# DXP.net
KiCad netlist of a schematic drawn in Altium Designer
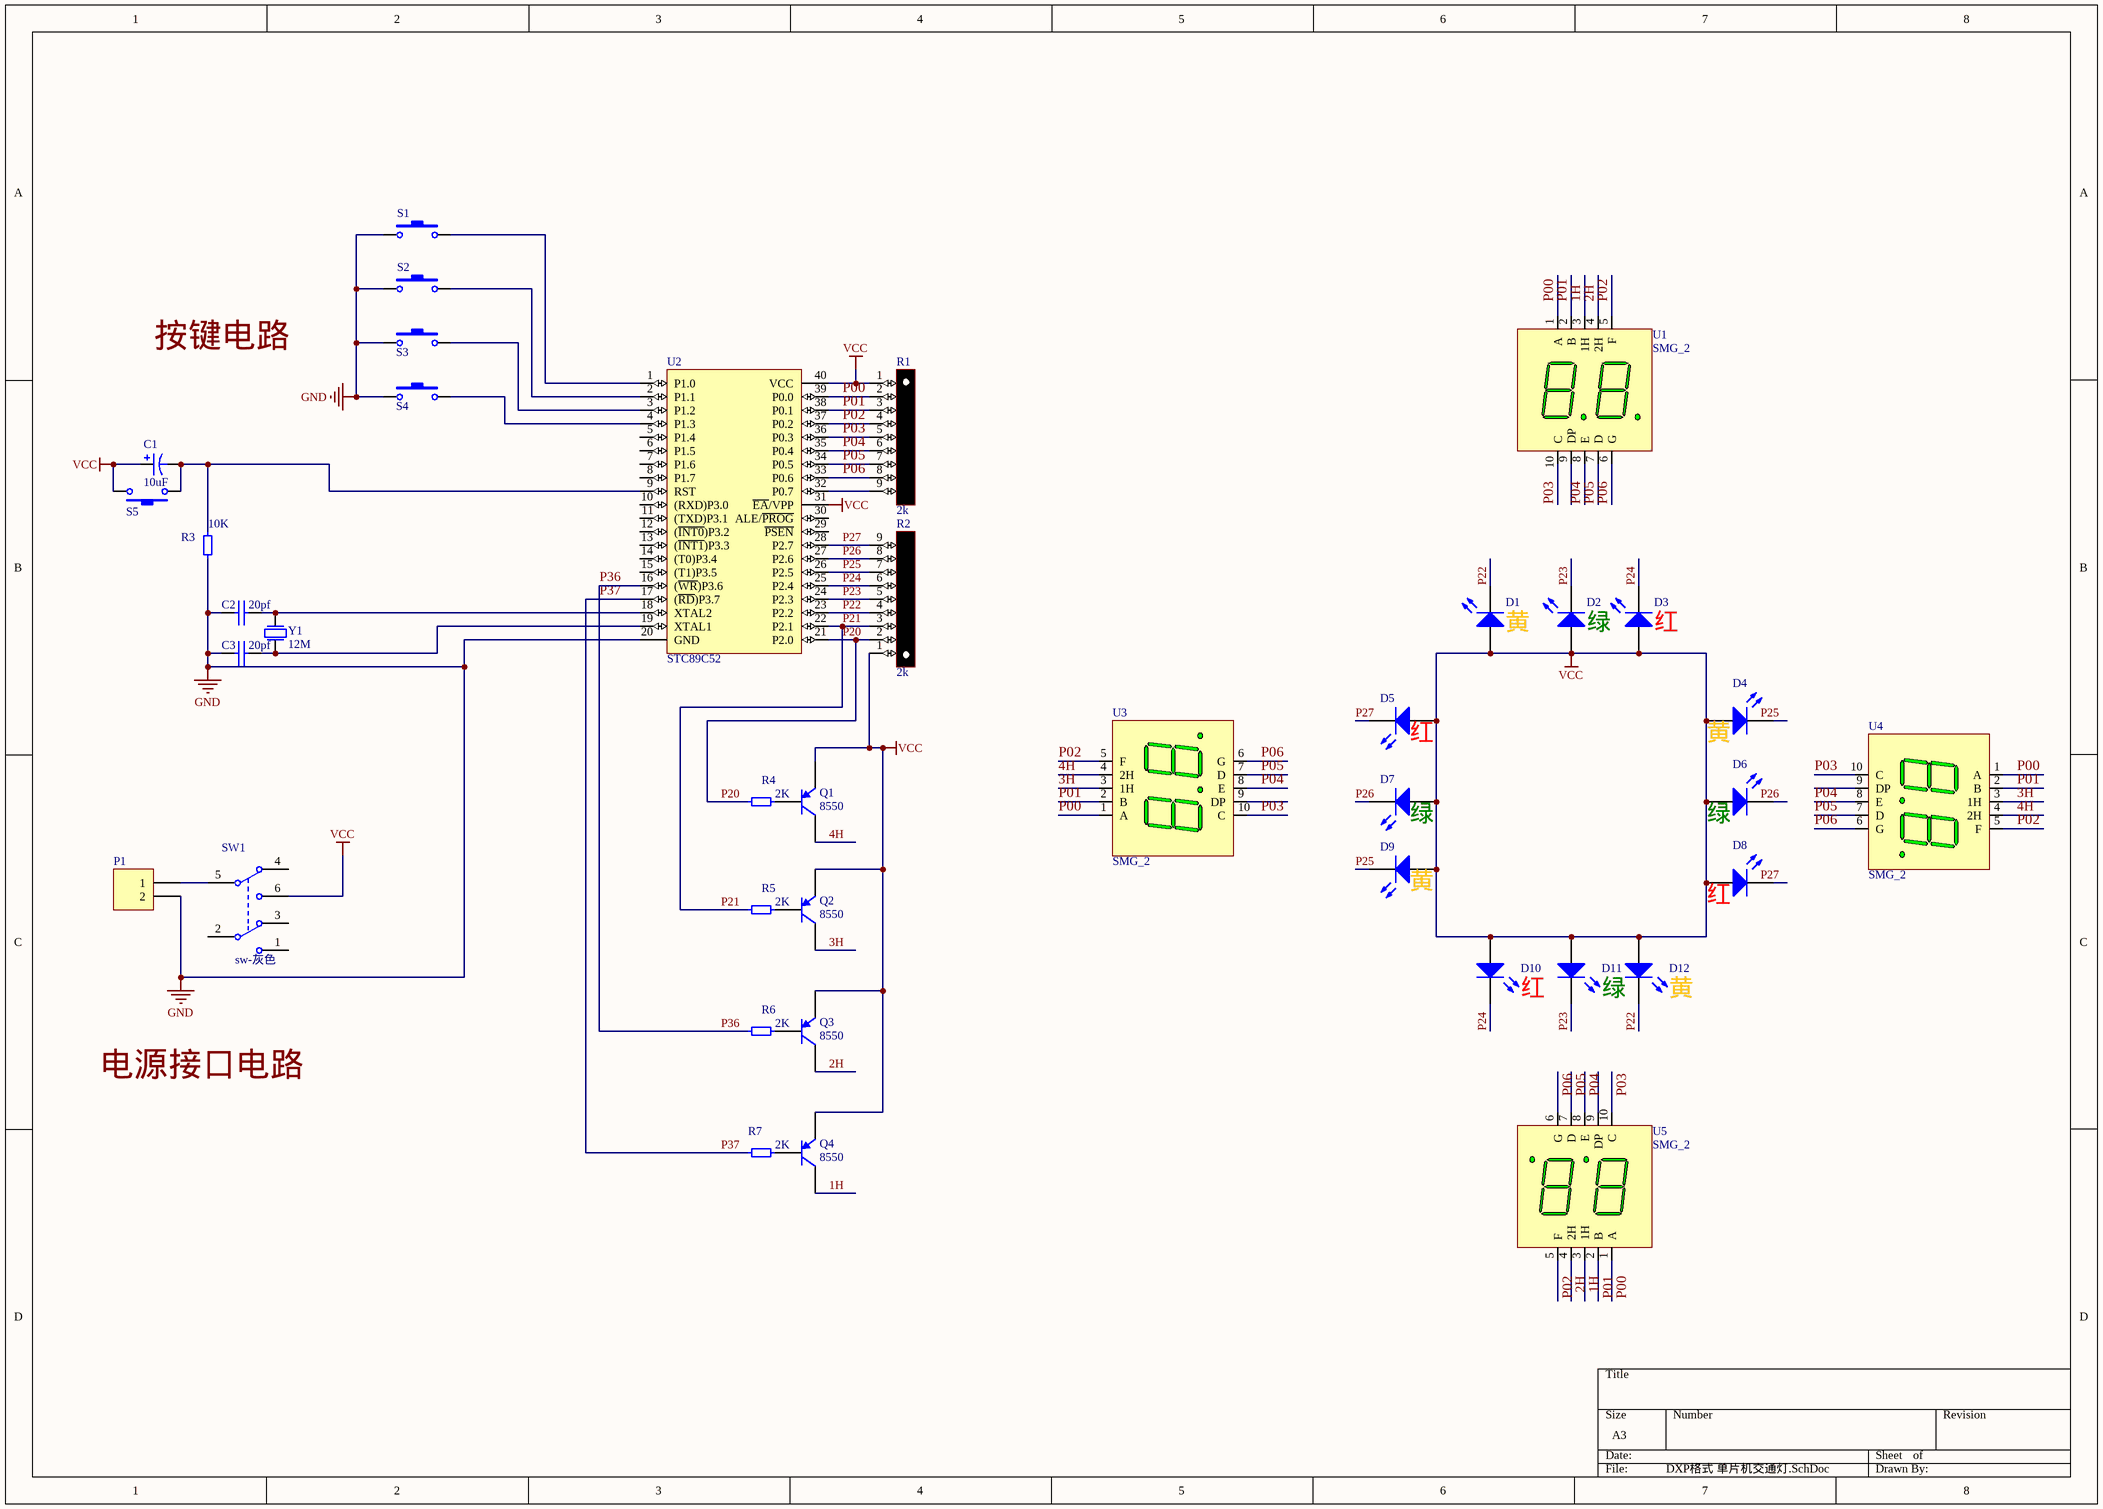
[diagram p0: DXP格式 单片机交通灯.SchDoc]

(export (version "E")
  (design (tool "Eeschema 10.0.6"))
  (components
    (comp (ref "C1")
      (value "10uF")
      (footprint "C_10")
      (description "Polarized Capacitor (Radial)")
      (fields (field (name "PUBLISHER") "Altium Limited"))
      (libsource (lib "简易动环监控系统") (part "Cap Pol1"))
    )
    (comp (ref "C2")
      (value "20pf")
      (footprint "CAP CP")
      (description "电容")
      (libsource (lib "C8051F020最小2") (part "CAP"))
    )
    (comp (ref "C3")
      (value "20pf")
      (footprint "CAP CP")
      (description "电容")
      (libsource (lib "C8051F020最小2") (part "CAP"))
    )
    (comp (ref "D1") (value "黄") (footprint "LED2J") (description "发光二极管") (libsource (lib "亮") (part "LED")))
    (comp (ref "D2") (value "绿") (footprint "LED2J") (description "发光二极管") (libsource (lib "亮") (part "LED")))
    (comp (ref "D3") (value "红") (footprint "LED2J") (description "发光二极管") (libsource (lib "亮") (part "LED")))
    (comp (ref "D4") (value "黄") (footprint "LED2J") (description "发光二极管") (libsource (lib "亮") (part "LED")))
    (comp (ref "D5") (value "红") (footprint "LED2J") (description "发光二极管") (libsource (lib "亮") (part "LED")))
    (comp (ref "D6") (value "绿") (footprint "LED2J") (description "发光二极管") (libsource (lib "亮") (part "LED")))
    (comp (ref "D7") (value "绿") (footprint "LED2J") (description "发光二极管") (libsource (lib "亮") (part "LED")))
    (comp (ref "D8") (value "红") (footprint "LED2J") (description "发光二极管") (libsource (lib "亮") (part "LED")))
    (comp (ref "D9") (value "黄") (footprint "LED2J") (description "发光二极管") (libsource (lib "亮") (part "LED")))
    (comp (ref "D10")
      (value "红")
      (footprint "LED2J")
      (description "发光二极管")
      (libsource (lib "亮") (part "LED"))
    )
    (comp (ref "D11")
      (value "绿")
      (footprint "LED2J")
      (description "发光二极管")
      (libsource (lib "亮") (part "LED"))
    )
    (comp (ref "D12")
      (value "黄")
      (footprint "LED2J")
      (description "发光二极管")
      (libsource (lib "亮") (part "LED"))
    )
    (comp (ref "P1")
      (value "Header 2")
      (footprint "POWER -  小电源座")
      (description "Header, 2-Pin")
      (fields (field (name "PUBLISHER") "Altium Limited"))
      (libsource (lib "Miscellaneous Connectors") (part "Header 2"))
    )
    (comp (ref "Q1")
      (value "8550")
      (footprint "s三极管直插")
      (description "PNP General Purpose Amplifier")
      (fields (field (name "PUBLISHER") "Altium Limited"))
      (libsource (lib "Miscellaneous Devices") (part "2N3906"))
    )
    (comp (ref "Q2")
      (value "8550")
      (footprint "s三极管直插")
      (description "PNP General Purpose Amplifier")
      (fields (field (name "PUBLISHER") "Altium Limited"))
      (libsource (lib "Miscellaneous Devices") (part "2N3906"))
    )
    (comp (ref "Q3")
      (value "8550")
      (footprint "s三极管直插")
      (description "PNP General Purpose Amplifier")
      (fields (field (name "PUBLISHER") "Altium Limited"))
      (libsource (lib "Miscellaneous Devices") (part "2N3906"))
    )
    (comp (ref "Q4")
      (value "8550")
      (footprint "s三极管直插")
      (description "PNP General Purpose Amplifier")
      (fields (field (name "PUBLISHER") "Altium Limited"))
      (libsource (lib "Miscellaneous Devices") (part "2N3906"))
    )
    (comp (ref "R1") (value "2k") (footprint "SIP9") (description "排阻") (libsource (lib "") (part "RES9_1")))
    (comp (ref "R2") (value "2k") (footprint "SIP9") (description "排阻") (libsource (lib "亮") (part "RES9")))
    (comp (ref "R3") (value "10K") (footprint "AXIAL0.3") (libsource (lib "C8051F020最小2") (part "RES2")))
    (comp (ref "R4") (value "2K") (footprint "AXIAL0.3") (libsource (lib "C8051F020最小2") (part "RES2")))
    (comp (ref "R5") (value "2K") (footprint "AXIAL0.3") (libsource (lib "C8051F020最小2") (part "RES2")))
    (comp (ref "R6") (value "2K") (footprint "AXIAL0.3") (libsource (lib "C8051F020最小2") (part "RES2")))
    (comp (ref "R7") (value "2K") (footprint "AXIAL0.3") (libsource (lib "C8051F020最小2") (part "RES2")))
    (comp (ref "S1")
      (value "SW-PB")
      (footprint "key")
      (description "Switch")
      (fields (field (name "PUBLISHER") "Altium Limited"))
      (libsource (lib "实验板原理图") (part "SW-PB"))
    )
    (comp (ref "S2")
      (value "SW-PB")
      (footprint "key")
      (description "Switch")
      (fields (field (name "PUBLISHER") "Altium Limited"))
      (libsource (lib "实验板原理图") (part "SW-PB"))
    )
    (comp (ref "S3")
      (value "SW-PB")
      (footprint "key")
      (description "Switch")
      (fields (field (name "PUBLISHER") "Altium Limited"))
      (libsource (lib "实验板原理图") (part "SW-PB"))
    )
    (comp (ref "S4")
      (value "SW-PB")
      (footprint "key")
      (description "Switch")
      (fields (field (name "PUBLISHER") "Altium Limited"))
      (libsource (lib "实验板原理图") (part "SW-PB"))
    )
    (comp (ref "S5")
      (value "SW-PB")
      (footprint "key")
      (description "Switch")
      (fields (field (name "PUBLISHER") "Altium Limited"))
      (libsource (lib "实验板原理图") (part "SW-PB"))
    )
    (comp (ref "SW1") (value "sw-灰色") (footprint "sw_自锁") (libsource (lib "JIANYANG") (part "sw-灰色")))
    (comp (ref "U1") (value "SMG_2") (footprint "SMG_2") (libsource (lib "") (part "SMG_2_2")))
    (comp (ref "U2") (value "STC89C52") (footprint "DIP40 - 做板") (libsource (lib "实验板原理图") (part "U1")))
    (comp (ref "U3") (value "SMG_2") (footprint "SMG_2") (libsource (lib "") (part "SMG_2_3")))
    (comp (ref "U4") (value "SMG_2") (footprint "SMG_2") (libsource (lib "交通灯+上下班高峰调整") (part "SMG_2")))
    (comp (ref "U5") (value "SMG_2") (footprint "SMG_2") (libsource (lib "") (part "SMG_2_1")))
    (comp (ref "Y1")
      (value "12M")
      (footprint "XTAL")
      (description "Crystal Oscillator")
      (libsource (lib "C8051F020最小2") (part "16M"))
    )
  )
  (nets
    (net (code "1") (name "/1H") (class "Default")
      (node (ref "Q4") (pin "3") (pinfunction "C_3") (pintype "passive"))
      (node (ref "U1") (pin "3") (pinfunction "1H_3") (pintype "passive"))
      (node (ref "U5") (pin "3") (pinfunction "1H_3") (pintype "passive"))
    )
    (net (code "2") (name "/2H") (class "Default")
      (node (ref "Q3") (pin "3") (pinfunction "C_3") (pintype "passive"))
      (node (ref "U1") (pin "4") (pinfunction "2H_4") (pintype "passive"))
      (node (ref "U5") (pin "4") (pinfunction "2H_4") (pintype "passive"))
    )
    (net (code "3") (name "/3H") (class "Default")
      (node (ref "Q2") (pin "3") (pinfunction "C_3") (pintype "passive"))
      (node (ref "U3") (pin "3") (pinfunction "1H_3") (pintype "passive"))
      (node (ref "U4") (pin "3") (pinfunction "1H_3") (pintype "passive"))
    )
    (net (code "4") (name "/4H") (class "Default")
      (node (ref "Q1") (pin "3") (pinfunction "C_3") (pintype "passive"))
      (node (ref "U3") (pin "4") (pinfunction "2H_4") (pintype "passive"))
      (node (ref "U4") (pin "4") (pinfunction "2H_4") (pintype "passive"))
    )
    (net (code "5") (name "/P00") (class "Default")
      (node (ref "R1") (pin "2") (pinfunction "2_2") (pintype "bidirectional"))
      (node (ref "U1") (pin "1") (pinfunction "A_1") (pintype "passive"))
      (node (ref "U2") (pin "39") (pinfunction "P0.0_39") (pintype "bidirectional"))
      (node (ref "U3") (pin "1") (pinfunction "A_1") (pintype "passive"))
      (node (ref "U4") (pin "1") (pinfunction "A_1") (pintype "passive"))
      (node (ref "U5") (pin "1") (pinfunction "A_1") (pintype "passive"))
    )
    (net (code "6") (name "/P01") (class "Default")
      (node (ref "R1") (pin "3") (pinfunction "3_3") (pintype "bidirectional"))
      (node (ref "U1") (pin "2") (pinfunction "B_2") (pintype "passive"))
      (node (ref "U2") (pin "38") (pinfunction "P0.1_38") (pintype "bidirectional"))
      (node (ref "U3") (pin "2") (pinfunction "B_2") (pintype "passive"))
      (node (ref "U4") (pin "2") (pinfunction "B_2") (pintype "passive"))
      (node (ref "U5") (pin "2") (pinfunction "B_2") (pintype "passive"))
    )
    (net (code "7") (name "/P02") (class "Default")
      (node (ref "R1") (pin "4") (pinfunction "4_4") (pintype "bidirectional"))
      (node (ref "U1") (pin "5") (pinfunction "F_5") (pintype "passive"))
      (node (ref "U2") (pin "37") (pinfunction "P0.2_37") (pintype "bidirectional"))
      (node (ref "U3") (pin "5") (pinfunction "F_5") (pintype "passive"))
      (node (ref "U4") (pin "5") (pinfunction "F_5") (pintype "passive"))
      (node (ref "U5") (pin "5") (pinfunction "F_5") (pintype "passive"))
    )
    (net (code "8") (name "/P03") (class "Default")
      (node (ref "R1") (pin "5") (pinfunction "5_5") (pintype "bidirectional"))
      (node (ref "U1") (pin "10") (pinfunction "C_10") (pintype "passive"))
      (node (ref "U2") (pin "36") (pinfunction "P0.3_36") (pintype "bidirectional"))
      (node (ref "U3") (pin "10") (pinfunction "C_10") (pintype "passive"))
      (node (ref "U4") (pin "10") (pinfunction "C_10") (pintype "passive"))
      (node (ref "U5") (pin "10") (pinfunction "C_10") (pintype "passive"))
    )
    (net (code "9") (name "/P04") (class "Default")
      (node (ref "R1") (pin "6") (pinfunction "6_6") (pintype "bidirectional"))
      (node (ref "U1") (pin "8") (pinfunction "E_8") (pintype "passive"))
      (node (ref "U2") (pin "35") (pinfunction "P0.4_35") (pintype "bidirectional"))
      (node (ref "U3") (pin "8") (pinfunction "E_8") (pintype "passive"))
      (node (ref "U4") (pin "8") (pinfunction "E_8") (pintype "passive"))
      (node (ref "U5") (pin "8") (pinfunction "E_8") (pintype "passive"))
    )
    (net (code "10") (name "/P05") (class "Default")
      (node (ref "R1") (pin "7") (pinfunction "7_7") (pintype "bidirectional"))
      (node (ref "U1") (pin "7") (pinfunction "D_7") (pintype "passive"))
      (node (ref "U2") (pin "34") (pinfunction "P0.5_34") (pintype "bidirectional"))
      (node (ref "U3") (pin "7") (pinfunction "D_7") (pintype "passive"))
      (node (ref "U4") (pin "7") (pinfunction "D_7") (pintype "passive"))
      (node (ref "U5") (pin "7") (pinfunction "D_7") (pintype "passive"))
    )
    (net (code "11") (name "/P06") (class "Default")
      (node (ref "R1") (pin "8") (pinfunction "8_8") (pintype "bidirectional"))
      (node (ref "U1") (pin "6") (pinfunction "G_6") (pintype "passive"))
      (node (ref "U2") (pin "33") (pinfunction "P0.6_33") (pintype "bidirectional"))
      (node (ref "U3") (pin "6") (pinfunction "G_6") (pintype "passive"))
      (node (ref "U4") (pin "6") (pinfunction "G_6") (pintype "passive"))
      (node (ref "U5") (pin "6") (pinfunction "G_6") (pintype "passive"))
    )
    (net (code "12") (name "/P20") (class "Default")
      (node (ref "R2") (pin "2") (pinfunction "2_2") (pintype "bidirectional"))
      (node (ref "R2") (pin "3") (pinfunction "3_3") (pintype "bidirectional"))
      (node (ref "R4") (pin "2") (pinfunction "2_2") (pintype "passive"))
      (node (ref "R5") (pin "2") (pinfunction "2_2") (pintype "passive"))
      (node (ref "U2") (pin "21") (pinfunction "P2.0_21") (pintype "bidirectional"))
      (node (ref "U2") (pin "22") (pinfunction "P2.1_22") (pintype "bidirectional"))
    )
    (net (code "13") (name "/P22") (class "Default")
      (node (ref "D1") (pin "2") (pinfunction "K_2") (pintype "passive"))
      (node (ref "D12") (pin "2") (pinfunction "K_2") (pintype "passive"))
      (node (ref "R2") (pin "4") (pinfunction "4_4") (pintype "bidirectional"))
      (node (ref "U2") (pin "23") (pinfunction "P2.2_23") (pintype "bidirectional"))
    )
    (net (code "14") (name "/P23") (class "Default")
      (node (ref "D11") (pin "2") (pinfunction "K_2") (pintype "passive"))
      (node (ref "D2") (pin "2") (pinfunction "K_2") (pintype "passive"))
      (node (ref "R2") (pin "5") (pinfunction "5_5") (pintype "bidirectional"))
      (node (ref "U2") (pin "24") (pinfunction "P2.3_24") (pintype "bidirectional"))
    )
    (net (code "15") (name "/P24") (class "Default")
      (node (ref "D10") (pin "2") (pinfunction "K_2") (pintype "passive"))
      (node (ref "D3") (pin "2") (pinfunction "K_2") (pintype "passive"))
      (node (ref "R2") (pin "6") (pinfunction "6_6") (pintype "bidirectional"))
      (node (ref "U2") (pin "25") (pinfunction "P2.4_25") (pintype "bidirectional"))
    )
    (net (code "16") (name "/P25") (class "Default")
      (node (ref "D9") (pin "2") (pinfunction "K_2") (pintype "passive"))
      (node (ref "R2") (pin "7") (pinfunction "7_7") (pintype "bidirectional"))
      (node (ref "U2") (pin "26") (pinfunction "P2.5_26") (pintype "bidirectional"))
    )
    (net (code "17") (name "/P26") (class "Default")
      (node (ref "D7") (pin "2") (pinfunction "K_2") (pintype "passive"))
      (node (ref "R2") (pin "8") (pinfunction "8_8") (pintype "bidirectional"))
      (node (ref "U2") (pin "27") (pinfunction "P2.6_27") (pintype "bidirectional"))
    )
    (net (code "18") (name "/P27") (class "Default")
      (node (ref "D5") (pin "2") (pinfunction "K_2") (pintype "passive"))
      (node (ref "R2") (pin "9") (pinfunction "9_9") (pintype "bidirectional"))
      (node (ref "U2") (pin "28") (pinfunction "P2.7_28") (pintype "bidirectional"))
    )
    (net (code "19") (name "/P36") (class "Default")
      (node (ref "R6") (pin "2") (pinfunction "2_2") (pintype "passive"))
      (node (ref "R7") (pin "2") (pinfunction "2_2") (pintype "passive"))
      (node (ref "U2") (pin "16") (pinfunction "(~{WR})P3.6_16") (pintype "bidirectional"))
      (node (ref "U2") (pin "17") (pinfunction "(~{RD})P3.7_17") (pintype "bidirectional"))
    )
    (net (code "22") (name "GND") (class "Default")
      (node (ref "C2") (pin "1") (pinfunction "1_1") (pintype "passive"))
      (node (ref "C3") (pin "1") (pinfunction "1_1") (pintype "passive"))
      (node (ref "P1") (pin "2") (pinfunction "2_2") (pintype "passive"))
      (node (ref "R3") (pin "1") (pinfunction "1_1") (pintype "passive"))
      (node (ref "S1") (pin "2") (pinfunction "2_2") (pintype "passive"))
      (node (ref "S2") (pin "2") (pinfunction "2_2") (pintype "passive"))
      (node (ref "S3") (pin "2") (pinfunction "2_2") (pintype "passive"))
      (node (ref "S4") (pin "2") (pinfunction "2_2") (pintype "passive"))
      (node (ref "U2") (pin "20") (pinfunction "GND_20") (pintype "power_in"))
    )
    (net (code "23") (name "Net-(Q1-B)") (class "Default")
      (node (ref "Q1") (pin "2") (pinfunction "B_2") (pintype "passive"))
      (node (ref "R4") (pin "1") (pinfunction "1_1") (pintype "passive"))
    )
    (net (code "24") (name "Net-(Q2-B)") (class "Default")
      (node (ref "Q2") (pin "2") (pinfunction "B_2") (pintype "passive"))
      (node (ref "R5") (pin "1") (pinfunction "1_1") (pintype "passive"))
    )
    (net (code "25") (name "Net-(Q3-B)") (class "Default")
      (node (ref "Q3") (pin "2") (pinfunction "B_2") (pintype "passive"))
      (node (ref "R6") (pin "1") (pinfunction "1_1") (pintype "passive"))
    )
    (net (code "26") (name "Net-(Q4-B)") (class "Default")
      (node (ref "Q4") (pin "2") (pinfunction "B_2") (pintype "passive"))
      (node (ref "R7") (pin "1") (pinfunction "1_1") (pintype "passive"))
    )
    (net (code "27") (name "Net-(SW1-COMMON1)") (class "Default")
      (node (ref "P1") (pin "1") (pinfunction "1_1") (pintype "passive"))
      (node (ref "SW1") (pin "5") (pinfunction "COMMON1_5") (pintype "passive"))
    )
    (net (code "28") (name "Net-(U2-P0.7)") (class "Default")
      (node (ref "R1") (pin "9") (pinfunction "9_9") (pintype "bidirectional"))
      (node (ref "U2") (pin "32") (pinfunction "P0.7_32") (pintype "bidirectional"))
    )
    (net (code "29") (name "Net-(U2-P1.0)") (class "Default")
      (node (ref "S1") (pin "1") (pinfunction "1_1") (pintype "passive"))
      (node (ref "U2") (pin "1") (pinfunction "P1.0_1") (pintype "bidirectional"))
    )
    (net (code "30") (name "Net-(U2-P1.1)") (class "Default")
      (node (ref "S2") (pin "1") (pinfunction "1_1") (pintype "passive"))
      (node (ref "U2") (pin "2") (pinfunction "P1.1_2") (pintype "bidirectional"))
    )
    (net (code "31") (name "Net-(U2-P1.2)") (class "Default")
      (node (ref "S3") (pin "1") (pinfunction "1_1") (pintype "passive"))
      (node (ref "U2") (pin "3") (pinfunction "P1.2_3") (pintype "bidirectional"))
    )
    (net (code "32") (name "Net-(U2-P1.3)") (class "Default")
      (node (ref "S4") (pin "1") (pinfunction "1_1") (pintype "passive"))
      (node (ref "U2") (pin "4") (pinfunction "P1.3_4") (pintype "bidirectional"))
    )
    (net (code "33") (name "Net-(U2-RST)") (class "Default")
      (node (ref "C1") (pin "2") (pinfunction "2_2") (pintype "passive"))
      (node (ref "R3") (pin "2") (pinfunction "2_2") (pintype "passive"))
      (node (ref "S5") (pin "1") (pinfunction "1_1") (pintype "passive"))
      (node (ref "U2") (pin "9") (pinfunction "RST_9") (pintype "bidirectional"))
    )
    (net (code "34") (name "Net-(U2-XTAL1)") (class "Default")
      (node (ref "C3") (pin "2") (pinfunction "2_2") (pintype "passive"))
      (node (ref "U2") (pin "19") (pinfunction "XTAL1_19") (pintype "bidirectional"))
      (node (ref "Y1") (pin "2") (pinfunction "P2_2") (pintype "passive"))
    )
    (net (code "35") (name "Net-(U2-XTAL2)") (class "Default")
      (node (ref "C2") (pin "2") (pinfunction "2_2") (pintype "passive"))
      (node (ref "U2") (pin "18") (pinfunction "XTAL2_18") (pintype "bidirectional"))
      (node (ref "Y1") (pin "1") (pinfunction "P1_1") (pintype "passive"))
    )
    (net (code "36") (name "VCC") (class "Default")
      (node (ref "C1") (pin "1") (pinfunction "1_1") (pintype "passive"))
      (node (ref "D1") (pin "1") (pinfunction "A_1") (pintype "passive"))
      (node (ref "D10") (pin "1") (pinfunction "A_1") (pintype "passive"))
      (node (ref "D11") (pin "1") (pinfunction "A_1") (pintype "passive"))
      (node (ref "D12") (pin "1") (pinfunction "A_1") (pintype "passive"))
      (node (ref "D2") (pin "1") (pinfunction "A_1") (pintype "passive"))
      (node (ref "D3") (pin "1") (pinfunction "A_1") (pintype "passive"))
      (node (ref "D4") (pin "1") (pinfunction "A_1") (pintype "passive"))
      (node (ref "D5") (pin "1") (pinfunction "A_1") (pintype "passive"))
      (node (ref "D6") (pin "1") (pinfunction "A_1") (pintype "passive"))
      (node (ref "D7") (pin "1") (pinfunction "A_1") (pintype "passive"))
      (node (ref "D8") (pin "1") (pinfunction "A_1") (pintype "passive"))
      (node (ref "D9") (pin "1") (pinfunction "A_1") (pintype "passive"))
      (node (ref "Q1") (pin "1") (pinfunction "E_1") (pintype "passive"))
      (node (ref "Q2") (pin "1") (pinfunction "E_1") (pintype "passive"))
      (node (ref "Q3") (pin "1") (pinfunction "E_1") (pintype "passive"))
      (node (ref "Q4") (pin "1") (pinfunction "E_1") (pintype "passive"))
      (node (ref "R1") (pin "1") (pinfunction "COM_1") (pintype "bidirectional"))
      (node (ref "R2") (pin "1") (pinfunction "COM_1") (pintype "bidirectional"))
      (node (ref "S5") (pin "2") (pinfunction "2_2") (pintype "passive"))
      (node (ref "SW1") (pin "6") (pinfunction "NO1_6") (pintype "passive"))
      (node (ref "U2") (pin "31") (pinfunction "~{EA}/VPP_31") (pintype "power_in"))
      (node (ref "U2") (pin "40") (pinfunction "VCC_40") (pintype "power_in"))
    )
    (net (code "37") (name "unconnected-(D4-K-Pad2)") (class "Default")
      (node (ref "D4") (pin "2") (pinfunction "K_2") (pintype "passive"))
    )
    (net (code "38") (name "unconnected-(D6-K-Pad2)") (class "Default")
      (node (ref "D6") (pin "2") (pinfunction "K_2") (pintype "passive"))
    )
    (net (code "39") (name "unconnected-(D8-K-Pad2)") (class "Default")
      (node (ref "D8") (pin "2") (pinfunction "K_2") (pintype "passive"))
    )
    (net (code "40") (name "unconnected-(SW1-COMMON2-Pad2)") (class "Default")
      (node (ref "SW1") (pin "2") (pinfunction "COMMON2_2") (pintype "passive"))
    )
    (net (code "41") (name "unconnected-(SW1-NC1-Pad4)") (class "Default")
      (node (ref "SW1") (pin "4") (pinfunction "NC1_4") (pintype "passive"))
    )
    (net (code "42") (name "unconnected-(SW1-NC2-Pad3)") (class "Default")
      (node (ref "SW1") (pin "3") (pinfunction "NC2_3") (pintype "passive"))
    )
    (net (code "43") (name "unconnected-(SW1-NO2-Pad1)") (class "Default")
      (node (ref "SW1") (pin "1") (pinfunction "NO2_1") (pintype "passive"))
    )
    (net (code "44") (name "unconnected-(U1-DP-Pad9)") (class "Default")
      (node (ref "U1") (pin "9") (pinfunction "DP_9") (pintype "passive"))
    )
    (net (code "45") (name "unconnected-(U2-(RXD)P3.0-Pad10)") (class "Default")
      (node (ref "U2") (pin "10") (pinfunction "(RXD)P3.0_10") (pintype "bidirectional"))
    )
    (net (code "46") (name "unconnected-(U2-(T0)P3.4-Pad14)") (class "Default")
      (node (ref "U2") (pin "14") (pinfunction "(T0)P3.4_14") (pintype "bidirectional"))
    )
    (net (code "47") (name "unconnected-(U2-(T1)P3.5-Pad15)") (class "Default")
      (node (ref "U2") (pin "15") (pinfunction "(T1)P3.5_15") (pintype "bidirectional"))
    )
    (net (code "48") (name "unconnected-(U2-(TXD)P3.1-Pad11)") (class "Default")
      (node (ref "U2") (pin "11") (pinfunction "(TXD)P3.1_11") (pintype "bidirectional"))
    )
    (net (code "49") (name "unconnected-(U2-(~{INT0})P3.2-Pad12)") (class "Default")
      (node (ref "U2") (pin "12") (pinfunction "(~{INT0})P3.2_12") (pintype "bidirectional"))
    )
    (net (code "50") (name "unconnected-(U2-(~{INT1})P3.3-Pad13)") (class "Default")
      (node (ref "U2") (pin "13") (pinfunction "(~{INT1})P3.3_13") (pintype "bidirectional"))
    )
    (net (code "51") (name "unconnected-(U2-ALE{slash}~{PROG}-Pad30)") (class "Default")
      (node (ref "U2") (pin "30") (pinfunction "ALE/~{PROG}_30") (pintype "bidirectional"))
    )
    (net (code "52") (name "unconnected-(U2-P1.4-Pad5)") (class "Default")
      (node (ref "U2") (pin "5") (pinfunction "P1.4_5") (pintype "bidirectional"))
    )
    (net (code "53") (name "unconnected-(U2-P1.5-Pad6)") (class "Default")
      (node (ref "U2") (pin "6") (pinfunction "P1.5_6") (pintype "bidirectional"))
    )
    (net (code "54") (name "unconnected-(U2-P1.6-Pad7)") (class "Default")
      (node (ref "U2") (pin "7") (pinfunction "P1.6_7") (pintype "bidirectional"))
    )
    (net (code "55") (name "unconnected-(U2-P1.7-Pad8)") (class "Default")
      (node (ref "U2") (pin "8") (pinfunction "P1.7_8") (pintype "bidirectional"))
    )
    (net (code "56") (name "unconnected-(U2-~{PSEN}-Pad29)") (class "Default")
      (node (ref "U2") (pin "29") (pinfunction "~{PSEN}_29") (pintype "bidirectional"))
    )
    (net (code "57") (name "unconnected-(U3-DP-Pad9)") (class "Default")
      (node (ref "U3") (pin "9") (pinfunction "DP_9") (pintype "passive"))
    )
    (net (code "58") (name "unconnected-(U4-DP-Pad9)") (class "Default")
      (node (ref "U4") (pin "9") (pinfunction "DP_9") (pintype "passive"))
    )
    (net (code "59") (name "unconnected-(U5-DP-Pad9)") (class "Default")
      (node (ref "U5") (pin "9") (pinfunction "DP_9") (pintype "passive"))
    )
  )
)
